# Sheet1.net
KiCad netlist of a schematic drawn in Altium Designer
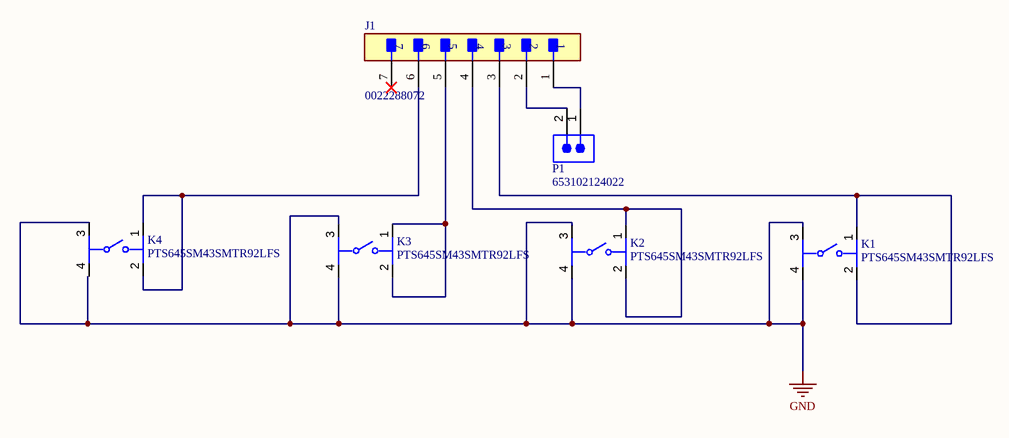
[diagram p0: Sheet1.SchDoc]

(export (version "E")
  (design (tool "Eeschema 10.0.6"))
  (components
    (comp (ref "J1")
      (value "0022288072")
      (footprint "FP-0022288072-MFG")
      (description "0022288072 KK 254 Breakaway Header Right-Angle Surface Mount Compatible 7 Circuits 0.38")
      (libsource (lib "Altium Content Vault") (part "5bcee6b94e1fee4be3f4cc3a650a442"))
    )
    (comp (ref "K1")
      (value "PTS645SM43SMTR92LFS")
      (footprint "FP-PTS645SM43SMTR92LFS-MFG")
      (description "SWITCH TACTILE SPST-NO 0.05A 12V")
      (libsource (lib "Altium Content Vault") (part "1adf0dd01260c80cf25a44bfd6b99ba"))
    )
    (comp (ref "K2")
      (value "PTS645SM43SMTR92LFS")
      (footprint "FP-PTS645SM43SMTR92LFS-MFG")
      (description "SWITCH TACTILE SPST-NO 0.05A 12V")
      (libsource (lib "Altium Content Vault") (part "1adf0dd01260c80cf25a44bfd6b99ba"))
    )
    (comp (ref "K3")
      (value "PTS645SM43SMTR92LFS")
      (footprint "FP-PTS645SM43SMTR92LFS-MFG")
      (description "SWITCH TACTILE SPST-NO 0.05A 12V")
      (libsource (lib "Altium Content Vault") (part "1adf0dd01260c80cf25a44bfd6b99ba"))
    )
    (comp (ref "K4")
      (value "PTS645SM43SMTR92LFS")
      (footprint "FP-PTS645SM43SMTR92LFS-MFG")
      (description "SWITCH TACTILE SPST-NO 0.05A 12V")
      (libsource (lib "Altium Content Vault") (part "1adf0dd01260c80cf25a44bfd6b99ba"))
    )
    (comp (ref "P1")
      (value "653102124022")
      (footprint "653102124022")
      (libsource (lib "Altium Content Vault") (part "Header_Male_1R_02P"))
    )
  )
  (nets
    (net (code "1") (name "GND") (class "Default")
      (node (ref "K1") (pin "3") (pinfunction "3_3") (pintype "passive"))
      (node (ref "K1") (pin "4") (pinfunction "4_4") (pintype "passive"))
      (node (ref "K2") (pin "3") (pinfunction "3_3") (pintype "passive"))
      (node (ref "K2") (pin "4") (pinfunction "4_4") (pintype "passive"))
      (node (ref "K3") (pin "3") (pinfunction "3_3") (pintype "passive"))
      (node (ref "K3") (pin "4") (pinfunction "4_4") (pintype "passive"))
      (node (ref "K4") (pin "3") (pinfunction "3_3") (pintype "passive"))
    )
    (net (code "2") (name "Net-(J1-Pad1)") (class "Default")
      (node (ref "J1") (pin "1") (pinfunction "1_1") (pintype "passive"))
      (node (ref "P1") (pin "1") (pinfunction "1_1") (pintype "passive"))
    )
    (net (code "3") (name "Net-(J1-Pad2)") (class "Default")
      (node (ref "J1") (pin "2") (pinfunction "2_2") (pintype "passive"))
      (node (ref "P1") (pin "2") (pinfunction "2_2") (pintype "passive"))
    )
    (net (code "4") (name "Net-(J1-Pad3)") (class "Default")
      (node (ref "J1") (pin "3") (pinfunction "3_3") (pintype "passive"))
      (node (ref "K1") (pin "1") (pinfunction "1_1") (pintype "passive"))
      (node (ref "K1") (pin "2") (pinfunction "2_2") (pintype "passive"))
    )
    (net (code "5") (name "Net-(J1-Pad4)") (class "Default")
      (node (ref "J1") (pin "4") (pinfunction "4_4") (pintype "passive"))
      (node (ref "K2") (pin "1") (pinfunction "1_1") (pintype "passive"))
      (node (ref "K2") (pin "2") (pinfunction "2_2") (pintype "passive"))
    )
    (net (code "6") (name "Net-(J1-Pad5)") (class "Default")
      (node (ref "J1") (pin "5") (pinfunction "5_5") (pintype "passive"))
      (node (ref "K3") (pin "1") (pinfunction "1_1") (pintype "passive"))
      (node (ref "K3") (pin "2") (pinfunction "2_2") (pintype "passive"))
    )
    (net (code "7") (name "Net-(J1-Pad6)") (class "Default")
      (node (ref "J1") (pin "6") (pinfunction "6_6") (pintype "passive"))
      (node (ref "K4") (pin "1") (pinfunction "1_1") (pintype "passive"))
      (node (ref "K4") (pin "2") (pinfunction "2_2") (pintype "passive"))
    )
    (net (code "8") (name "unconnected-(J1-Pad7)") (class "Default")
      (node (ref "J1") (pin "7") (pinfunction "7_7") (pintype "passive+no_connect"))
    )
    (net (code "9") (name "unconnected-(K4-Pad4)") (class "Default")
      (node (ref "K4") (pin "4") (pinfunction "4_4") (pintype "passive"))
    )
  )
)
